# ep-project-team12-2.net
KiCad netlist of a schematic drawn in EAGLE
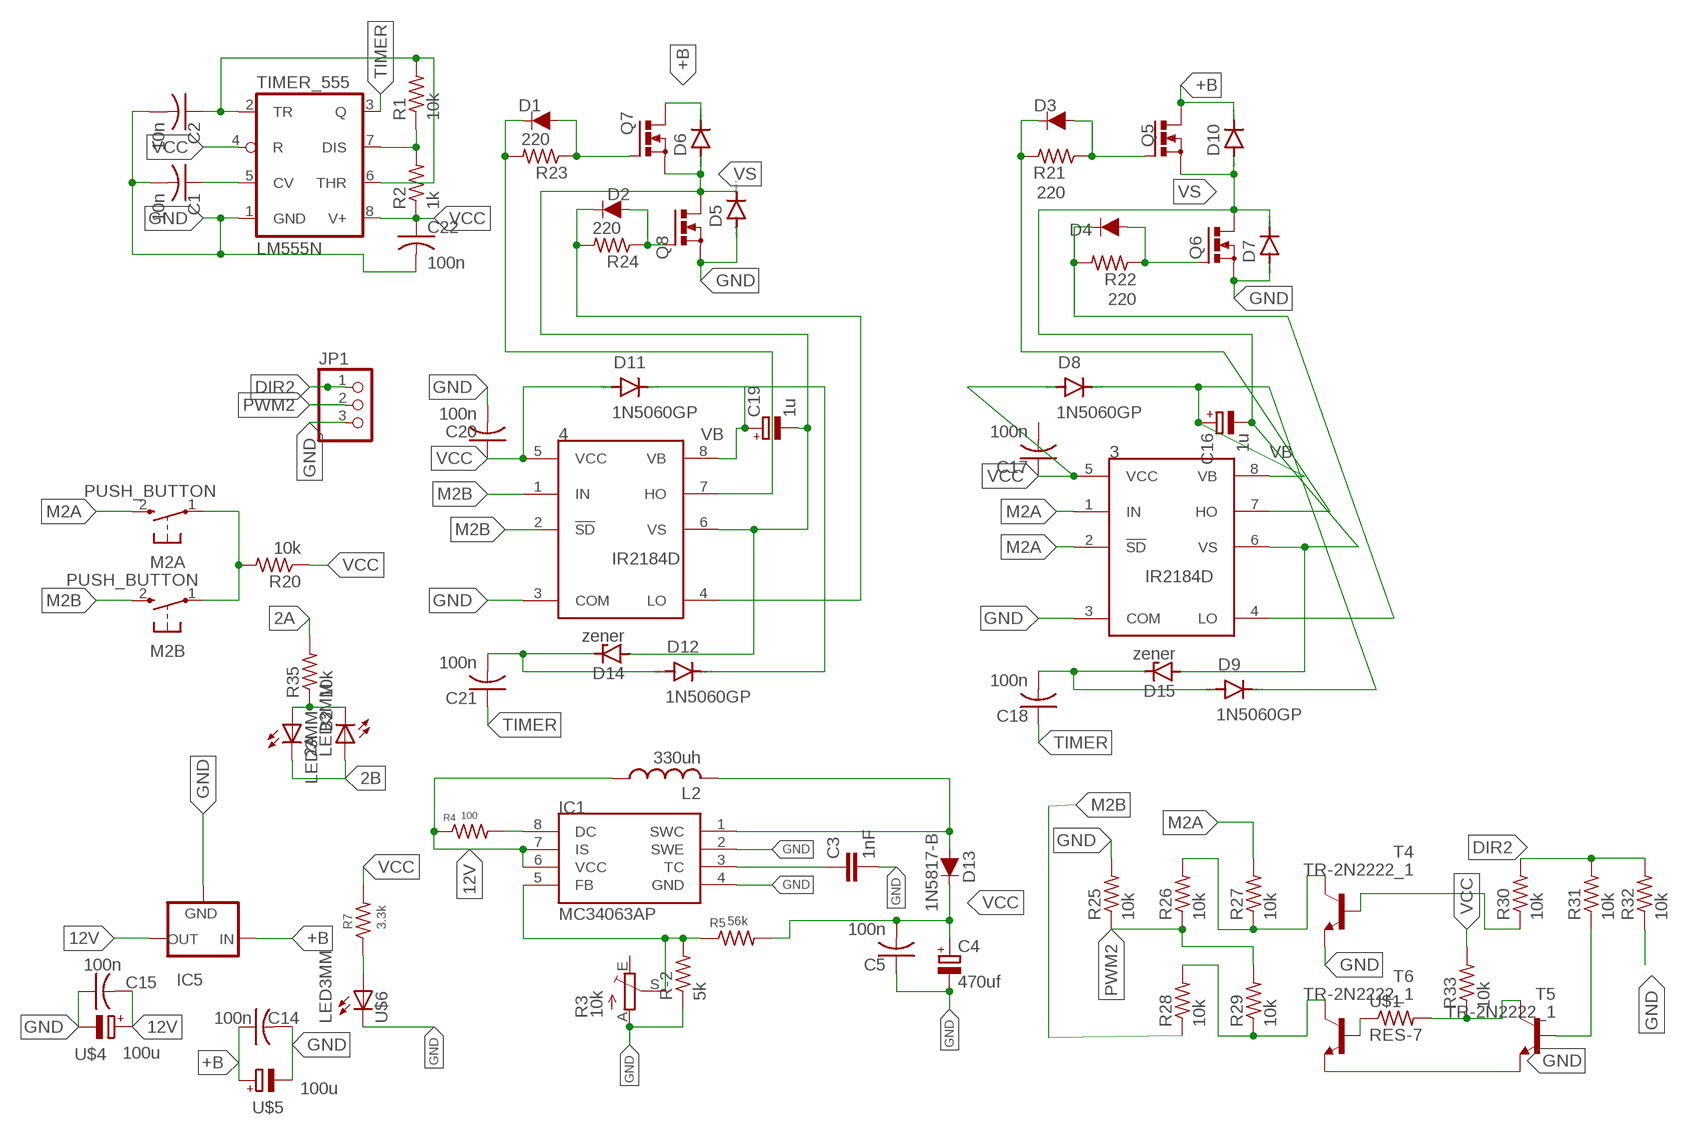
[diagram p0: schematic, sheet 1]

(export (version "E")
  (design (tool "Eeschema 10.0.6"))
  (components
    (comp (ref "2A")
      (value "LED3MM")
      (footprint "eagle-import:LED3MM")
      (libsource (lib "eagle-import") (part "LED3MM"))
    )
    (comp (ref "3")
      (value "IR2184D")
      (footprint "eagle-import:DIL08")
      (libsource (lib "eagle-import") (part "IR2184D"))
    )
    (comp (ref "4")
      (value "IR2184D")
      (footprint "eagle-import:DIL08")
      (libsource (lib "eagle-import") (part "IR2184D"))
    )
    (comp (ref "B2")
      (value "LED3MM")
      (footprint "eagle-import:LED3MM")
      (libsource (lib "eagle-import") (part "LED3MM"))
    )
    (comp (ref "C1")
      (value "10n")
      (footprint "eagle-import:C025-025X050")
      (libsource (lib "eagle-import") (part "C-US025-025X050"))
    )
    (comp (ref "C2")
      (value "10n")
      (footprint "eagle-import:C025-025X050")
      (libsource (lib "eagle-import") (part "C-US025-025X050"))
    )
    (comp (ref "C3")
      (value "1nF")
      (footprint "eagle-import:C025-025X050")
      (fields (field (name "SPICEPREFIX") "C"))
      (libsource (lib "eagle-import") (part "CAPACITOR"))
    )
    (comp (ref "C4")
      (value "470uf")
      (footprint "eagle-import:E3,5-8")
      (fields (field (name "SPICEPREFIX") "C"))
      (libsource (lib "eagle-import") (part "CAP_POL"))
    )
    (comp (ref "C5")
      (value "100n")
      (footprint "eagle-import:C025-025X050")
      (libsource (lib "eagle-import") (part "C-US025-025X050"))
    )
    (comp (ref "C14")
      (value "100n")
      (footprint "eagle-import:C025-025X050")
      (libsource (lib "eagle-import") (part "C-US025-025X050"))
    )
    (comp (ref "C15")
      (value "100n")
      (footprint "eagle-import:C025-025X050")
      (libsource (lib "eagle-import") (part "C-US025-025X050"))
    )
    (comp (ref "C16")
      (value "1u")
      (footprint "eagle-import:E5-5")
      (libsource (lib "eagle-import") (part "CPOL-EUE5-5"))
    )
    (comp (ref "C17")
      (value "100n")
      (footprint "eagle-import:C025-025X050")
      (libsource (lib "eagle-import") (part "C-US025-025X050"))
    )
    (comp (ref "C18")
      (value "100n")
      (footprint "eagle-import:C025-025X050")
      (libsource (lib "eagle-import") (part "C-US025-025X050"))
    )
    (comp (ref "C19")
      (value "1u")
      (footprint "eagle-import:E5-5")
      (libsource (lib "eagle-import") (part "CPOL-EUE5-5"))
    )
    (comp (ref "C20")
      (value "100n")
      (footprint "eagle-import:C025-025X050")
      (libsource (lib "eagle-import") (part "C-US025-025X050"))
    )
    (comp (ref "C21")
      (value "100n")
      (footprint "eagle-import:C025-025X050")
      (libsource (lib "eagle-import") (part "C-US025-025X050"))
    )
    (comp (ref "C22")
      (value "100n")
      (footprint "eagle-import:C025-025X050")
      (libsource (lib "eagle-import") (part "C-US025-025X050"))
    )
    (comp (ref "D1")
      (value "1A/50V/1.1V")
      (footprint "eagle-import:DIODE-1N4001")
      (libsource (lib "eagle-import") (part "DIODE(1A)-PTH"))
    )
    (comp (ref "D2")
      (value "1A/50V/1.1V")
      (footprint "eagle-import:DIODE-1N4001")
      (libsource (lib "eagle-import") (part "DIODE(1A)-PTH"))
    )
    (comp (ref "D3")
      (value "1A/50V/1.1V")
      (footprint "eagle-import:DIODE-1N4001")
      (libsource (lib "eagle-import") (part "DIODE(1A)-PTH"))
    )
    (comp (ref "D4")
      (value "1A/50V/1.1V")
      (footprint "eagle-import:DIODE-1N4001")
      (libsource (lib "eagle-import") (part "DIODE(1A)-PTH"))
    )
    (comp (ref "D5")
      (value "BY396")
      (footprint "eagle-import:DO201-15")
      (libsource (lib "eagle-import") (part "BY396"))
    )
    (comp (ref "D6")
      (value "BY396")
      (footprint "eagle-import:DO201-15")
      (libsource (lib "eagle-import") (part "BY396"))
    )
    (comp (ref "D7")
      (value "BY396")
      (footprint "eagle-import:DO201-15")
      (libsource (lib "eagle-import") (part "BY396"))
    )
    (comp (ref "D8")
      (value "1N5060GP")
      (footprint "eagle-import:DO15-12")
      (libsource (lib "eagle-import") (part "1N5060GP"))
    )
    (comp (ref "D9")
      (value "1N5060GP")
      (footprint "eagle-import:DO15-12")
      (libsource (lib "eagle-import") (part "1N5060GP"))
    )
    (comp (ref "D10")
      (value "BY396")
      (footprint "eagle-import:DO201-15")
      (libsource (lib "eagle-import") (part "BY396"))
    )
    (comp (ref "D11")
      (value "1N5060GP")
      (footprint "eagle-import:DO15-12")
      (libsource (lib "eagle-import") (part "1N5060GP"))
    )
    (comp (ref "D12")
      (value "1N5060GP")
      (footprint "eagle-import:DO15-12")
      (libsource (lib "eagle-import") (part "1N5060GP"))
    )
    (comp (ref "D13")
      (value "1N5817-B")
      (footprint "eagle-import:DIODE-1N4001")
      (fields (field (name "SPICEPREFIX") "D"))
      (libsource (lib "eagle-import") (part "DIODE(1A)-PTH"))
    )
    (comp (ref "D14")
      (value "zener")
      (footprint "eagle-import:SOD81")
      (libsource (lib "eagle-import") (part "BZD23"))
    )
    (comp (ref "D15")
      (value "zener")
      (footprint "eagle-import:SOD81")
      (libsource (lib "eagle-import") (part "BZD23"))
    )
    (comp (ref "IC1")
      (value "MC34063AP")
      (footprint "eagle-import:DIL08")
      (fields (field (name "SPICEPREFIX") "X"))
      (libsource (lib "eagle-import") (part "MC34063AP"))
    )
    (comp (ref "IC5")
      (value "78XXS")
      (footprint "eagle-import:78XXS")
      (libsource (lib "eagle-import") (part "78XXS"))
    )
    (comp (ref "JP1")
      (value "PINHD-3_DATA")
      (footprint "eagle-import:1X03_DATA")
      (libsource (lib "eagle-import") (part "PINHD-3_DATA"))
    )
    (comp (ref "L2")
      (value "330uh")
      (footprint "eagle-import:POWER-CHOKE_WE-TPC")
      (libsource (lib "eagle-import") (part "L-USWE-TPC"))
    )
    (comp (ref "M2A")
      (value "PUSH_BUTTON")
      (footprint "eagle-import:B3F-10XX")
      (libsource (lib "eagle-import") (part "PUSH_BUTTON"))
    )
    (comp (ref "M2B")
      (value "PUSH_BUTTON")
      (footprint "eagle-import:B3F-10XX")
      (libsource (lib "eagle-import") (part "PUSH_BUTTON"))
    )
    (comp (ref "Q5")
      (value "MOSFET_NTO220BV")
      (footprint "eagle-import:TO220BV")
      (libsource (lib "eagle-import") (part "MOSFET_NTO220BV"))
    )
    (comp (ref "Q6")
      (value "MOSFET_NTO220BV")
      (footprint "eagle-import:TO220BV")
      (libsource (lib "eagle-import") (part "MOSFET_NTO220BV"))
    )
    (comp (ref "Q7")
      (value "MOSFET_NTO220BV")
      (footprint "eagle-import:TO220BV")
      (libsource (lib "eagle-import") (part "MOSFET_NTO220BV"))
    )
    (comp (ref "Q8")
      (value "MOSFET_NTO220BV")
      (footprint "eagle-import:TO220BV")
      (libsource (lib "eagle-import") (part "MOSFET_NTO220BV"))
    )
    (comp (ref "R-2")
      (value "5k")
      (footprint "eagle-import:0204_7")
      (libsource (lib "eagle-import") (part "RES-7"))
    )
    (comp (ref "R1")
      (value "10k")
      (footprint "eagle-import:0204_7")
      (libsource (lib "eagle-import") (part "R-US_0204/7"))
    )
    (comp (ref "R2")
      (value "1k")
      (footprint "eagle-import:0204_7")
      (libsource (lib "eagle-import") (part "R-US_0204/7"))
    )
    (comp (ref "R3")
      (value "10k")
      (footprint "eagle-import:CA6V")
      (fields (field (name "SPICEPREFIX") "J"))
      (libsource (lib "eagle-import") (part "TRIM_EU-CA6V"))
    )
    (comp (ref "R4")
      (value "100")
      (footprint "eagle-import:0204_7")
      (fields (field (name "SPICEPREFIX") "R"))
      (libsource (lib "eagle-import") (part "RES-7"))
    )
    (comp (ref "R5")
      (value "56k")
      (footprint "eagle-import:0204_7")
      (fields (field (name "SPICEPREFIX") "R"))
      (libsource (lib "eagle-import") (part "RES-7"))
    )
    (comp (ref "R7")
      (value "3.3k")
      (footprint "eagle-import:0204_7")
      (fields (field (name "SPICEPREFIX") "R"))
      (libsource (lib "eagle-import") (part "RES-7"))
    )
    (comp (ref "R20")
      (value "10k")
      (footprint "eagle-import:0204_7")
      (libsource (lib "eagle-import") (part "R-US_0204/7"))
    )
    (comp (ref "R21")
      (value "220")
      (footprint "eagle-import:0204_7")
      (libsource (lib "eagle-import") (part "R-US_0204/7"))
    )
    (comp (ref "R22")
      (value "220")
      (footprint "eagle-import:0204_7")
      (libsource (lib "eagle-import") (part "R-US_0204/7"))
    )
    (comp (ref "R23")
      (value "220")
      (footprint "eagle-import:0204_7")
      (libsource (lib "eagle-import") (part "R-US_0204/7"))
    )
    (comp (ref "R24")
      (value "220")
      (footprint "eagle-import:0204_7")
      (libsource (lib "eagle-import") (part "R-US_0204/7"))
    )
    (comp (ref "R25")
      (value "10k")
      (footprint "eagle-import:0204_7")
      (libsource (lib "eagle-import") (part "R-US_0204/7"))
    )
    (comp (ref "R26")
      (value "10k")
      (footprint "eagle-import:0204_7")
      (libsource (lib "eagle-import") (part "R-US_0204/7"))
    )
    (comp (ref "R27")
      (value "10k")
      (footprint "eagle-import:0204_7")
      (libsource (lib "eagle-import") (part "R-US_0204/7"))
    )
    (comp (ref "R28")
      (value "10k")
      (footprint "eagle-import:0204_7")
      (libsource (lib "eagle-import") (part "R-US_0204/7"))
    )
    (comp (ref "R29")
      (value "10k")
      (footprint "eagle-import:0204_7")
      (libsource (lib "eagle-import") (part "R-US_0204/7"))
    )
    (comp (ref "R30")
      (value "10k")
      (footprint "eagle-import:0204_7")
      (libsource (lib "eagle-import") (part "R-US_0204/7"))
    )
    (comp (ref "R31")
      (value "10k")
      (footprint "eagle-import:0204_7")
      (libsource (lib "eagle-import") (part "R-US_0204/7"))
    )
    (comp (ref "R32")
      (value "10k")
      (footprint "eagle-import:0204_7")
      (libsource (lib "eagle-import") (part "R-US_0204/7"))
    )
    (comp (ref "R33")
      (value "10k")
      (footprint "eagle-import:0204_7")
      (libsource (lib "eagle-import") (part "R-US_0204/7"))
    )
    (comp (ref "R35")
      (value "10k")
      (footprint "eagle-import:0204_7")
      (libsource (lib "eagle-import") (part "R-US_0204/7"))
    )
    (comp (ref "T4")
      (value "TR-2N2222_1")
      (footprint "eagle-import:TO92-EBC")
      (fields (field (name "SPICEPREFIX") "J"))
      (libsource (lib "eagle-import") (part "TR-2N2222_1"))
    )
    (comp (ref "T5")
      (value "TR-2N2222_1")
      (footprint "eagle-import:TO92-EBC")
      (fields (field (name "SPICEPREFIX") "J"))
      (libsource (lib "eagle-import") (part "TR-2N2222_1"))
    )
    (comp (ref "T6")
      (value "TR-2N2222_1")
      (footprint "eagle-import:TO92-EBC")
      (fields (field (name "SPICEPREFIX") "J"))
      (libsource (lib "eagle-import") (part "TR-2N2222_1"))
    )
    (comp (ref "TIMER_555")
      (value "LM555N")
      (footprint "eagle-import:DIL08")
      (libsource (lib "eagle-import") (part "555NLM"))
    )
    (comp (ref "U$1")
      (value "RES-7")
      (footprint "eagle-import:0204_7")
      (fields (field (name "SPICEPREFIX") "B"))
      (libsource (lib "eagle-import") (part "RES-7"))
    )
    (comp (ref "U$4")
      (value "100u")
      (footprint "eagle-import:E3,5-8")
      (libsource (lib "eagle-import") (part "CAP_POL"))
    )
    (comp (ref "U$5")
      (value "100u")
      (footprint "eagle-import:E3,5-8")
      (libsource (lib "eagle-import") (part "CAP_POL"))
    )
    (comp (ref "U$6")
      (value "LED3MM")
      (footprint "eagle-import:LED3MM")
      (fields (field (name "SPICEPREFIX") "B"))
      (libsource (lib "eagle-import") (part "LED3MM"))
    )
  )
  (nets
    (net (code "1") (name "+B") (class "Default")
      (node (ref "C14") (pin "1") (pinfunction "1_1") (pintype "passive"))
      (node (ref "D10") (pin "C") (pinfunction "C_C") (pintype "passive"))
      (node (ref "D6") (pin "C") (pinfunction "C_C") (pintype "passive"))
      (node (ref "IC5") (pin "IN") (pinfunction "IN_IN") (pintype "input"))
      (node (ref "Q5") (pin "D") (pinfunction "D_D") (pintype "passive"))
      (node (ref "Q7") (pin "D") (pinfunction "D_D") (pintype "passive"))
      (node (ref "U$5") (pin "+") (pinfunction "+_+") (pintype "passive"))
    )
    (net (code "2") (name "2A") (class "Default")
      (node (ref "R35") (pin "2") (pinfunction "2_2") (pintype "passive"))
    )
    (net (code "3") (name "2B") (class "Default")
      (node (ref "2A") (pin "K") (pinfunction "C_K") (pintype "passive"))
      (node (ref "B2") (pin "A") (pinfunction "A_A") (pintype "passive"))
    )
    (net (code "4") (name "12V") (class "Default")
      (node (ref "C15") (pin "2") (pinfunction "2_2") (pintype "passive"))
      (node (ref "IC1") (pin "6") (pinfunction "VCC_6") (pintype "passive"))
      (node (ref "IC1") (pin "7") (pinfunction "IS_7") (pintype "passive"))
      (node (ref "IC5") (pin "OUT") (pinfunction "OUT_OUT") (pintype "passive"))
      (node (ref "L2") (pin "1") (pinfunction "1_1") (pintype "passive"))
      (node (ref "R4") (pin "1") (pinfunction "1_1") (pintype "passive"))
      (node (ref "U$4") (pin "+") (pinfunction "+_+") (pintype "passive"))
    )
    (net (code "5") (name "DIR2") (class "Default")
      (node (ref "JP1") (pin "1") (pinfunction "1_1") (pintype "passive"))
      (node (ref "R30") (pin "2") (pinfunction "2_2") (pintype "passive"))
      (node (ref "R31") (pin "2") (pinfunction "2_2") (pintype "passive"))
      (node (ref "R32") (pin "2") (pinfunction "2_2") (pintype "passive"))
    )
    (net (code "6") (name "GND") (class "Default")
      (node (ref "3") (pin "3") (pinfunction "COM_3") (pintype "power_in"))
      (node (ref "4") (pin "3") (pinfunction "COM_3") (pintype "power_in"))
      (node (ref "C1") (pin "2") (pinfunction "2_2") (pintype "passive"))
      (node (ref "C14") (pin "2") (pinfunction "2_2") (pintype "passive"))
      (node (ref "C15") (pin "1") (pinfunction "1_1") (pintype "passive"))
      (node (ref "C2") (pin "2") (pinfunction "2_2") (pintype "passive"))
      (node (ref "C20") (pin "2") (pinfunction "2_2") (pintype "passive"))
      (node (ref "C22") (pin "2") (pinfunction "2_2") (pintype "passive"))
      (node (ref "C3") (pin "2") (pinfunction "2_2") (pintype "passive"))
      (node (ref "C4") (pin "-") (pinfunction "-_-") (pintype "passive"))
      (node (ref "C5") (pin "1") (pinfunction "1_1") (pintype "passive"))
      (node (ref "D5") (pin "A") (pinfunction "A_A") (pintype "passive"))
      (node (ref "D7") (pin "A") (pinfunction "A_A") (pintype "passive"))
      (node (ref "IC1") (pin "2") (pinfunction "SWE_2") (pintype "passive"))
      (node (ref "IC1") (pin "4") (pinfunction "GND_4") (pintype "passive"))
      (node (ref "IC5") (pin "GND") (pinfunction "GND_GND") (pintype "input"))
      (node (ref "JP1") (pin "3") (pinfunction "3_3") (pintype "passive"))
      (node (ref "Q6") (pin "S") (pinfunction "S_S") (pintype "passive"))
      (node (ref "Q8") (pin "S") (pinfunction "S_S") (pintype "passive"))
      (node (ref "R-2") (pin "1") (pinfunction "1_1") (pintype "passive"))
      (node (ref "R25") (pin "2") (pinfunction "2_2") (pintype "passive"))
      (node (ref "R3") (pin "A") (pinfunction "A_A") (pintype "passive"))
      (node (ref "R32") (pin "1") (pinfunction "1_1") (pintype "passive"))
      (node (ref "T4") (pin "E") (pinfunction "E_E") (pintype "passive"))
      (node (ref "T5") (pin "E") (pinfunction "E_E") (pintype "passive"))
      (node (ref "T6") (pin "E") (pinfunction "E_E") (pintype "passive"))
      (node (ref "TIMER_555") (pin "1") (pinfunction "GND_1") (pintype "power_in"))
      (node (ref "U$4") (pin "-") (pinfunction "-_-") (pintype "passive"))
      (node (ref "U$5") (pin "-") (pinfunction "-_-") (pintype "passive"))
      (node (ref "U$6") (pin "K") (pinfunction "C_K") (pintype "passive"))
    )
    (net (code "7") (name "M2A") (class "Default")
      (node (ref "3") (pin "1") (pinfunction "IN_1") (pintype "input"))
      (node (ref "3") (pin "2") (pinfunction "~{SD}_2") (pintype "input"))
      (node (ref "M2A") (pin "2") (pinfunction "S_2") (pintype "passive"))
      (node (ref "R27") (pin "2") (pinfunction "2_2") (pintype "passive"))
    )
    (net (code "8") (name "M2B") (class "Default")
      (node (ref "4") (pin "1") (pinfunction "IN_1") (pintype "input"))
      (node (ref "4") (pin "2") (pinfunction "~{SD}_2") (pintype "input"))
      (node (ref "M2B") (pin "2") (pinfunction "S_2") (pintype "passive"))
      (node (ref "R28") (pin "1") (pinfunction "1_1") (pintype "passive"))
    )
    (net (code "9") (name "Net-(3-HO)") (class "Default")
      (node (ref "3") (pin "7") (pinfunction "HO_7") (pintype "output"))
      (node (ref "D3") (pin "C") (pinfunction "C_C") (pintype "passive"))
      (node (ref "R21") (pin "2") (pinfunction "2_2") (pintype "passive"))
    )
    (net (code "10") (name "Net-(3-LO)") (class "Default")
      (node (ref "3") (pin "4") (pinfunction "LO_4") (pintype "output"))
      (node (ref "D4") (pin "C") (pinfunction "C_C") (pintype "passive"))
      (node (ref "R22") (pin "2") (pinfunction "2_2") (pintype "passive"))
    )
    (net (code "11") (name "Net-(4-HO)") (class "Default")
      (node (ref "4") (pin "7") (pinfunction "HO_7") (pintype "output"))
      (node (ref "D1") (pin "C") (pinfunction "C_C") (pintype "passive"))
      (node (ref "R23") (pin "2") (pinfunction "2_2") (pintype "passive"))
    )
    (net (code "12") (name "Net-(4-LO)") (class "Default")
      (node (ref "4") (pin "4") (pinfunction "LO_4") (pintype "output"))
      (node (ref "D2") (pin "C") (pinfunction "C_C") (pintype "passive"))
      (node (ref "R24") (pin "2") (pinfunction "2_2") (pintype "passive"))
    )
    (net (code "13") (name "Net-(B2-C)") (class "Default")
      (node (ref "2A") (pin "A") (pinfunction "A_A") (pintype "passive"))
      (node (ref "B2") (pin "K") (pinfunction "C_K") (pintype "passive"))
      (node (ref "R35") (pin "1") (pinfunction "1_1") (pintype "passive"))
    )
    (net (code "14") (name "Net-(C18-Pad2)") (class "Default")
      (node (ref "C18") (pin "2") (pinfunction "2_2") (pintype "passive"))
      (node (ref "D15") (pin "C") (pinfunction "C_C") (pintype "passive"))
      (node (ref "D9") (pin "A") (pinfunction "A_A") (pintype "passive"))
    )
    (net (code "15") (name "Net-(C21-Pad2)") (class "Default")
      (node (ref "C21") (pin "2") (pinfunction "2_2") (pintype "passive"))
      (node (ref "D12") (pin "A") (pinfunction "A_A") (pintype "passive"))
      (node (ref "D14") (pin "C") (pinfunction "C_C") (pintype "passive"))
    )
    (net (code "16") (name "Net-(D1-PadA)") (class "Default")
      (node (ref "D1") (pin "A") (pinfunction "A_A") (pintype "passive"))
      (node (ref "Q7") (pin "G") (pinfunction "G_G") (pintype "passive"))
      (node (ref "R23") (pin "1") (pinfunction "1_1") (pintype "passive"))
    )
    (net (code "17") (name "Net-(D2-PadA)") (class "Default")
      (node (ref "D2") (pin "A") (pinfunction "A_A") (pintype "passive"))
      (node (ref "Q8") (pin "G") (pinfunction "G_G") (pintype "passive"))
      (node (ref "R24") (pin "1") (pinfunction "1_1") (pintype "passive"))
    )
    (net (code "18") (name "Net-(D3-PadA)") (class "Default")
      (node (ref "D3") (pin "A") (pinfunction "A_A") (pintype "passive"))
      (node (ref "Q5") (pin "G") (pinfunction "G_G") (pintype "passive"))
      (node (ref "R21") (pin "1") (pinfunction "1_1") (pintype "passive"))
    )
    (net (code "19") (name "Net-(D4-PadA)") (class "Default")
      (node (ref "D4") (pin "A") (pinfunction "A_A") (pintype "passive"))
      (node (ref "Q6") (pin "G") (pinfunction "G_G") (pintype "passive"))
      (node (ref "R22") (pin "1") (pinfunction "1_1") (pintype "passive"))
    )
    (net (code "20") (name "Net-(IC1-DC)") (class "Default")
      (node (ref "IC1") (pin "8") (pinfunction "DC_8") (pintype "passive"))
      (node (ref "R4") (pin "2") (pinfunction "2_2") (pintype "passive"))
    )
    (net (code "21") (name "Net-(IC1-FB)") (class "Default")
      (node (ref "IC1") (pin "5") (pinfunction "FB_5") (pintype "passive"))
      (node (ref "R-2") (pin "2") (pinfunction "2_2") (pintype "passive"))
      (node (ref "R3") (pin "S") (pinfunction "S_S") (pintype "passive"))
      (node (ref "R5") (pin "1") (pinfunction "1_1") (pintype "passive"))
    )
    (net (code "22") (name "Net-(IC1-SWC)") (class "Default")
      (node (ref "D13") (pin "A") (pinfunction "A_A") (pintype "passive"))
      (node (ref "IC1") (pin "1") (pinfunction "SWC_1") (pintype "passive"))
      (node (ref "L2") (pin "2") (pinfunction "2_2") (pintype "passive"))
    )
    (net (code "23") (name "Net-(IC1-TC)") (class "Default")
      (node (ref "C3") (pin "1") (pinfunction "1_1") (pintype "passive"))
      (node (ref "IC1") (pin "3") (pinfunction "TC_3") (pintype "passive"))
    )
    (net (code "24") (name "Net-(M2A-P)") (class "Default")
      (node (ref "M2A") (pin "1") (pinfunction "P_1") (pintype "passive"))
      (node (ref "M2B") (pin "1") (pinfunction "P_1") (pintype "passive"))
      (node (ref "R20") (pin "2") (pinfunction "2_2") (pintype "passive"))
    )
    (net (code "25") (name "Net-(R7-Pad1)") (class "Default")
      (node (ref "R7") (pin "1") (pinfunction "1_1") (pintype "passive"))
      (node (ref "U$6") (pin "A") (pinfunction "A_A") (pintype "passive"))
    )
    (net (code "26") (name "Net-(R26-Pad2)") (class "Default")
      (node (ref "R26") (pin "2") (pinfunction "2_2") (pintype "passive"))
      (node (ref "R27") (pin "1") (pinfunction "1_1") (pintype "passive"))
      (node (ref "T4") (pin "C") (pinfunction "C_C") (pintype "passive"))
    )
    (net (code "27") (name "Net-(R28-Pad2)") (class "Default")
      (node (ref "R28") (pin "2") (pinfunction "2_2") (pintype "passive"))
      (node (ref "R29") (pin "1") (pinfunction "1_1") (pintype "passive"))
      (node (ref "T6") (pin "C") (pinfunction "C_C") (pintype "passive"))
    )
    (net (code "28") (name "Net-(R30-Pad1)") (class "Default")
      (node (ref "R30") (pin "1") (pinfunction "1_1") (pintype "passive"))
      (node (ref "T4") (pin "B") (pinfunction "B_B") (pintype "passive"))
    )
    (net (code "29") (name "Net-(R31-Pad1)") (class "Default")
      (node (ref "R31") (pin "1") (pinfunction "1_1") (pintype "passive"))
      (node (ref "T5") (pin "B") (pinfunction "B_B") (pintype "passive"))
    )
    (net (code "30") (name "Net-(R33-Pad1)") (class "Default")
      (node (ref "R33") (pin "1") (pinfunction "1_1") (pintype "passive"))
      (node (ref "T5") (pin "C") (pinfunction "C_C") (pintype "passive"))
      (node (ref "U$1") (pin "2") (pinfunction "2_2") (pintype "passive"))
    )
    (net (code "31") (name "Net-(T6-PadB)") (class "Default")
      (node (ref "T6") (pin "B") (pinfunction "B_B") (pintype "passive"))
      (node (ref "U$1") (pin "1") (pinfunction "1_1") (pintype "passive"))
    )
    (net (code "32") (name "Net-(TIMER_555-CV)") (class "Default")
      (node (ref "C1") (pin "1") (pinfunction "1_1") (pintype "passive"))
      (node (ref "TIMER_555") (pin "5") (pinfunction "CV_5") (pintype "input"))
    )
    (net (code "33") (name "Net-(TIMER_555-DIS)") (class "Default")
      (node (ref "R1") (pin "1") (pinfunction "1_1") (pintype "passive"))
      (node (ref "R2") (pin "2") (pinfunction "2_2") (pintype "passive"))
      (node (ref "TIMER_555") (pin "7") (pinfunction "DIS_7") (pintype "input"))
    )
    (net (code "34") (name "Net-(TIMER_555-THR)") (class "Default")
      (node (ref "C2") (pin "1") (pinfunction "1_1") (pintype "passive"))
      (node (ref "R1") (pin "2") (pinfunction "2_2") (pintype "passive"))
      (node (ref "TIMER_555") (pin "2") (pinfunction "TR_2") (pintype "input"))
      (node (ref "TIMER_555") (pin "6") (pinfunction "THR_6") (pintype "input"))
    )
    (net (code "35") (name "PWM2") (class "Default")
      (node (ref "JP1") (pin "2") (pinfunction "2_2") (pintype "passive"))
      (node (ref "R25") (pin "1") (pinfunction "1_1") (pintype "passive"))
      (node (ref "R26") (pin "1") (pinfunction "1_1") (pintype "passive"))
      (node (ref "R29") (pin "2") (pinfunction "2_2") (pintype "passive"))
    )
    (net (code "36") (name "TIMER") (class "Default")
      (node (ref "C18") (pin "1") (pinfunction "1_1") (pintype "passive"))
      (node (ref "C21") (pin "1") (pinfunction "1_1") (pintype "passive"))
      (node (ref "TIMER_555") (pin "3") (pinfunction "Q_3") (pintype "output"))
    )
    (net (code "37") (name "VB") (class "Default")
      (node (ref "3") (pin "8") (pinfunction "VB_8") (pintype "power_in"))
      (node (ref "4") (pin "8") (pinfunction "VB_8") (pintype "power_in"))
      (node (ref "C16") (pin "+") (pinfunction "+_+") (pintype "passive"))
      (node (ref "C19") (pin "+") (pinfunction "+_+") (pintype "passive"))
      (node (ref "D11") (pin "C") (pinfunction "C_C") (pintype "passive"))
      (node (ref "D12") (pin "C") (pinfunction "C_C") (pintype "passive"))
      (node (ref "D8") (pin "C") (pinfunction "C_C") (pintype "passive"))
      (node (ref "D9") (pin "C") (pinfunction "C_C") (pintype "passive"))
    )
    (net (code "38") (name "VCC") (class "Default")
      (node (ref "3") (pin "5") (pinfunction "VCC_5") (pintype "power_in"))
      (node (ref "4") (pin "5") (pinfunction "VCC_5") (pintype "power_in"))
      (node (ref "C17") (pin "1") (pinfunction "1_1") (pintype "passive"))
      (node (ref "C20") (pin "1") (pinfunction "1_1") (pintype "passive"))
      (node (ref "C22") (pin "1") (pinfunction "1_1") (pintype "passive"))
      (node (ref "C4") (pin "+") (pinfunction "+_+") (pintype "passive"))
      (node (ref "C5") (pin "2") (pinfunction "2_2") (pintype "passive"))
      (node (ref "D11") (pin "A") (pinfunction "A_A") (pintype "passive"))
      (node (ref "D13") (pin "C") (pinfunction "C_C") (pintype "passive"))
      (node (ref "D8") (pin "A") (pinfunction "A_A") (pintype "passive"))
      (node (ref "R2") (pin "1") (pinfunction "1_1") (pintype "passive"))
      (node (ref "R20") (pin "1") (pinfunction "1_1") (pintype "passive"))
      (node (ref "R33") (pin "2") (pinfunction "2_2") (pintype "passive"))
      (node (ref "R5") (pin "2") (pinfunction "2_2") (pintype "passive"))
      (node (ref "R7") (pin "2") (pinfunction "2_2") (pintype "passive"))
      (node (ref "TIMER_555") (pin "4") (pinfunction "R_4") (pintype "input"))
      (node (ref "TIMER_555") (pin "8") (pinfunction "V+_8") (pintype "power_in"))
    )
    (net (code "39") (name "VS") (class "Default")
      (node (ref "3") (pin "6") (pinfunction "VS_6") (pintype "power_in"))
      (node (ref "4") (pin "6") (pinfunction "VS_6") (pintype "power_in"))
      (node (ref "C16") (pin "-") (pinfunction "-_-") (pintype "passive"))
      (node (ref "C19") (pin "-") (pinfunction "-_-") (pintype "passive"))
      (node (ref "D10") (pin "A") (pinfunction "A_A") (pintype "passive"))
      (node (ref "D14") (pin "A") (pinfunction "A_A") (pintype "passive"))
      (node (ref "D15") (pin "A") (pinfunction "A_A") (pintype "passive"))
      (node (ref "D5") (pin "C") (pinfunction "C_C") (pintype "passive"))
      (node (ref "D6") (pin "A") (pinfunction "A_A") (pintype "passive"))
      (node (ref "D7") (pin "C") (pinfunction "C_C") (pintype "passive"))
      (node (ref "Q5") (pin "S") (pinfunction "S_S") (pintype "passive"))
      (node (ref "Q6") (pin "D") (pinfunction "D_D") (pintype "passive"))
      (node (ref "Q7") (pin "S") (pinfunction "S_S") (pintype "passive"))
      (node (ref "Q8") (pin "D") (pinfunction "D_D") (pintype "passive"))
    )
    (net (code "40") (name "unconnected-(C17-Pad2)") (class "Default")
      (node (ref "C17") (pin "2") (pinfunction "2_2") (pintype "passive"))
    )
    (net (code "41") (name "unconnected-(R3-PadE)") (class "Default")
      (node (ref "R3") (pin "E") (pinfunction "E_E") (pintype "passive"))
    )
  )
)
